# base_revA.net
KiCad netlist of a schematic drawn in EAGLE
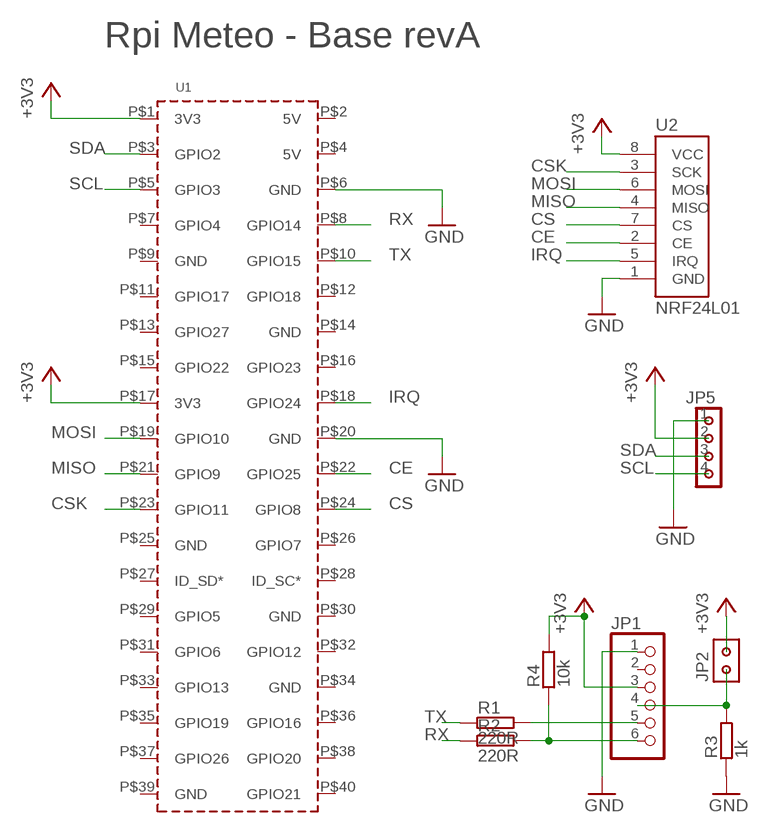
[diagram p0: schematic, sheet 1]

(export (version "E")
  (design (tool "Eeschema 10.0.6"))
  (components
    (comp (ref "JP1")
      (value "PINHD-1X6")
      (footprint "eagle-import:1X06")
      (libsource (lib "eagle-import") (part "PINHD-1X6"))
    )
    (comp (ref "JP2")
      (value "PINHD-2X1")
      (footprint "eagle-import:PINHD-2X1")
      (libsource (lib "eagle-import") (part "PINHD-2X1"))
    )
    (comp (ref "JP5")
      (value "PINHD-4X1'BASIC'")
      (footprint "eagle-import:1X04")
      (libsource (lib "eagle-import") (part "PINHD-4X1'BASIC'"))
    )
    (comp (ref "R1")
      (value "220R")
      (footprint "eagle-import:0207-10")
      (libsource (lib "eagle-import") (part "R-0207/10"))
    )
    (comp (ref "R2")
      (value "220R")
      (footprint "eagle-import:0207-10")
      (libsource (lib "eagle-import") (part "R-0207/10"))
    )
    (comp (ref "R3")
      (value "1k")
      (footprint "eagle-import:0207-10")
      (libsource (lib "eagle-import") (part "R-0207/10"))
    )
    (comp (ref "R4")
      (value "10k")
      (footprint "eagle-import:0207-10")
      (libsource (lib "eagle-import") (part "R-0207/10"))
    )
    (comp (ref "U1")
      (value "RPI3_SIMPLE'FULL'")
      (footprint "eagle-import:RPI3")
      (libsource (lib "eagle-import") (part "RPI3_SIMPLE'FULL'"))
    )
    (comp (ref "U2")
      (value "NRF24L01")
      (footprint "eagle-import:NRF24L01")
      (libsource (lib "eagle-import") (part "NRF24L01"))
    )
  )
  (nets
    (net (code "1") (name "+3V3") (class "Default")
      (node (ref "JP1") (pin "3") (pinfunction "3_3") (pintype "passive"))
      (node (ref "JP2") (pin "1") (pinfunction "1_1") (pintype "input"))
      (node (ref "JP5") (pin "2") (pinfunction "2_2") (pintype "passive"))
      (node (ref "R4") (pin "2") (pinfunction "P$2_2") (pintype "bidirectional"))
      (node (ref "U1") (pin "P$1") (pinfunction "3V3_P$1") (pintype "bidirectional"))
      (node (ref "U1") (pin "P$17") (pinfunction "3V3_P$17") (pintype "bidirectional"))
      (node (ref "U2") (pin "8") (pinfunction "VCC_8") (pintype "power_in"))
    )
    (net (code "2") (name "/CE") (class "Default")
      (node (ref "U1") (pin "P$22") (pinfunction "GPIO25_P$22") (pintype "bidirectional"))
      (node (ref "U2") (pin "2") (pinfunction "CE_2") (pintype "bidirectional"))
    )
    (net (code "3") (name "/CS") (class "Default")
      (node (ref "U1") (pin "P$24") (pinfunction "GPIO8_P$24") (pintype "bidirectional"))
      (node (ref "U2") (pin "7") (pinfunction "CS_7") (pintype "bidirectional"))
    )
    (net (code "4") (name "/CSK") (class "Default")
      (node (ref "U1") (pin "P$23") (pinfunction "GPIO11_P$23") (pintype "bidirectional"))
      (node (ref "U2") (pin "3") (pinfunction "SCK_3") (pintype "bidirectional"))
    )
    (net (code "5") (name "/IRQ") (class "Default")
      (node (ref "U1") (pin "P$18") (pinfunction "GPIO24_P$18") (pintype "bidirectional"))
      (node (ref "U2") (pin "5") (pinfunction "IRQ_5") (pintype "bidirectional"))
    )
    (net (code "6") (name "/MISO") (class "Default")
      (node (ref "U1") (pin "P$21") (pinfunction "GPIO9_P$21") (pintype "bidirectional"))
      (node (ref "U2") (pin "4") (pinfunction "MISO_4") (pintype "bidirectional"))
    )
    (net (code "7") (name "/MOSI") (class "Default")
      (node (ref "U1") (pin "P$19") (pinfunction "GPIO10_P$19") (pintype "bidirectional"))
      (node (ref "U2") (pin "6") (pinfunction "MOSI_6") (pintype "bidirectional"))
    )
    (net (code "8") (name "/RX") (class "Default")
      (node (ref "R2") (pin "1") (pinfunction "P$1_1") (pintype "bidirectional"))
      (node (ref "U1") (pin "P$8") (pinfunction "GPIO14_P$8") (pintype "bidirectional"))
    )
    (net (code "9") (name "/SCL") (class "Default")
      (node (ref "JP5") (pin "4") (pinfunction "4_4") (pintype "passive"))
      (node (ref "U1") (pin "P$5") (pinfunction "GPIO3_P$5") (pintype "bidirectional"))
    )
    (net (code "10") (name "/SDA") (class "Default")
      (node (ref "JP5") (pin "3") (pinfunction "3_3") (pintype "passive"))
      (node (ref "U1") (pin "P$3") (pinfunction "GPIO2_P$3") (pintype "bidirectional"))
    )
    (net (code "11") (name "/TX") (class "Default")
      (node (ref "R1") (pin "1") (pinfunction "P$1_1") (pintype "bidirectional"))
      (node (ref "U1") (pin "P$10") (pinfunction "GPIO15_P$10") (pintype "bidirectional"))
    )
    (net (code "12") (name "GND") (class "Default")
      (node (ref "JP1") (pin "1") (pinfunction "1_1") (pintype "passive"))
      (node (ref "JP5") (pin "1") (pinfunction "1_1") (pintype "passive"))
      (node (ref "R3") (pin "1") (pinfunction "P$1_1") (pintype "bidirectional"))
      (node (ref "U1") (pin "P$20") (pinfunction "GND_P$20") (pintype "bidirectional"))
      (node (ref "U1") (pin "P$6") (pinfunction "GND_P$6") (pintype "bidirectional"))
      (node (ref "U2") (pin "1") (pinfunction "GND_1") (pintype "power_in"))
    )
    (net (code "13") (name "Net-(R1-P$2)") (class "Default")
      (node (ref "JP1") (pin "5") (pinfunction "5_5") (pintype "passive"))
      (node (ref "R1") (pin "2") (pinfunction "P$2_2") (pintype "bidirectional"))
    )
    (net (code "14") (name "Net-(R2-P$2)") (class "Default")
      (node (ref "JP1") (pin "6") (pinfunction "6_6") (pintype "passive"))
      (node (ref "R2") (pin "2") (pinfunction "P$2_2") (pintype "bidirectional"))
      (node (ref "R4") (pin "1") (pinfunction "P$1_1") (pintype "bidirectional"))
    )
    (net (code "15") (name "Net-(R3-P$2)") (class "Default")
      (node (ref "JP1") (pin "4") (pinfunction "4_4") (pintype "passive"))
      (node (ref "JP2") (pin "2") (pinfunction "2_2") (pintype "bidirectional"))
      (node (ref "R3") (pin "2") (pinfunction "P$2_2") (pintype "bidirectional"))
    )
    (net (code "16") (name "unconnected-(JP1-Pad2)") (class "Default")
      (node (ref "JP1") (pin "2") (pinfunction "2_2") (pintype "passive"))
    )
    (net (code "17") (name "unconnected-(U1-5V-PadP$2)") (class "Default")
      (node (ref "U1") (pin "P$2") (pinfunction "5V_P$2") (pintype "bidirectional"))
    )
    (net (code "18") (name "unconnected-(U1-5V-PadP$4)") (class "Default")
      (node (ref "U1") (pin "P$4") (pinfunction "5V_P$4") (pintype "bidirectional"))
    )
    (net (code "19") (name "unconnected-(U1-GND-PadP$9)") (class "Default")
      (node (ref "U1") (pin "P$9") (pinfunction "GND_P$9") (pintype "bidirectional"))
    )
    (net (code "20") (name "unconnected-(U1-GND-PadP$14)") (class "Default")
      (node (ref "U1") (pin "P$14") (pinfunction "GND_P$14") (pintype "bidirectional"))
    )
    (net (code "21") (name "unconnected-(U1-GND-PadP$25)") (class "Default")
      (node (ref "U1") (pin "P$25") (pinfunction "GND_P$25") (pintype "bidirectional"))
    )
    (net (code "22") (name "unconnected-(U1-GND-PadP$30)") (class "Default")
      (node (ref "U1") (pin "P$30") (pinfunction "GND_P$30") (pintype "bidirectional"))
    )
    (net (code "23") (name "unconnected-(U1-GND-PadP$34)") (class "Default")
      (node (ref "U1") (pin "P$34") (pinfunction "GND_P$34") (pintype "bidirectional"))
    )
    (net (code "24") (name "unconnected-(U1-GND-PadP$39)") (class "Default")
      (node (ref "U1") (pin "P$39") (pinfunction "GND_P$39") (pintype "bidirectional"))
    )
    (net (code "25") (name "unconnected-(U1-GPIO4-PadP$7)") (class "Default")
      (node (ref "U1") (pin "P$7") (pinfunction "GPIO4_P$7") (pintype "bidirectional"))
    )
    (net (code "26") (name "unconnected-(U1-GPIO5-PadP$29)") (class "Default")
      (node (ref "U1") (pin "P$29") (pinfunction "GPIO5_P$29") (pintype "bidirectional"))
    )
    (net (code "27") (name "unconnected-(U1-GPIO6-PadP$31)") (class "Default")
      (node (ref "U1") (pin "P$31") (pinfunction "GPIO6_P$31") (pintype "bidirectional"))
    )
    (net (code "28") (name "unconnected-(U1-GPIO7-PadP$26)") (class "Default")
      (node (ref "U1") (pin "P$26") (pinfunction "GPIO7_P$26") (pintype "bidirectional"))
    )
    (net (code "29") (name "unconnected-(U1-GPIO12-PadP$32)") (class "Default")
      (node (ref "U1") (pin "P$32") (pinfunction "GPIO12_P$32") (pintype "bidirectional"))
    )
    (net (code "30") (name "unconnected-(U1-GPIO13-PadP$33)") (class "Default")
      (node (ref "U1") (pin "P$33") (pinfunction "GPIO13_P$33") (pintype "bidirectional"))
    )
    (net (code "31") (name "unconnected-(U1-GPIO16-PadP$36)") (class "Default")
      (node (ref "U1") (pin "P$36") (pinfunction "GPIO16_P$36") (pintype "bidirectional"))
    )
    (net (code "32") (name "unconnected-(U1-GPIO17-PadP$11)") (class "Default")
      (node (ref "U1") (pin "P$11") (pinfunction "GPIO17_P$11") (pintype "bidirectional"))
    )
    (net (code "33") (name "unconnected-(U1-GPIO18-PadP$12)") (class "Default")
      (node (ref "U1") (pin "P$12") (pinfunction "GPIO18_P$12") (pintype "bidirectional"))
    )
    (net (code "34") (name "unconnected-(U1-GPIO19-PadP$35)") (class "Default")
      (node (ref "U1") (pin "P$35") (pinfunction "GPIO19_P$35") (pintype "bidirectional"))
    )
    (net (code "35") (name "unconnected-(U1-GPIO20-PadP$38)") (class "Default")
      (node (ref "U1") (pin "P$38") (pinfunction "GPIO20_P$38") (pintype "bidirectional"))
    )
    (net (code "36") (name "unconnected-(U1-GPIO21-PadP$40)") (class "Default")
      (node (ref "U1") (pin "P$40") (pinfunction "GPIO21_P$40") (pintype "bidirectional"))
    )
    (net (code "37") (name "unconnected-(U1-GPIO22-PadP$15)") (class "Default")
      (node (ref "U1") (pin "P$15") (pinfunction "GPIO22_P$15") (pintype "bidirectional"))
    )
    (net (code "38") (name "unconnected-(U1-GPIO23-PadP$16)") (class "Default")
      (node (ref "U1") (pin "P$16") (pinfunction "GPIO23_P$16") (pintype "bidirectional"))
    )
    (net (code "39") (name "unconnected-(U1-GPIO26-PadP$37)") (class "Default")
      (node (ref "U1") (pin "P$37") (pinfunction "GPIO26_P$37") (pintype "bidirectional"))
    )
    (net (code "40") (name "unconnected-(U1-GPIO27-PadP$13)") (class "Default")
      (node (ref "U1") (pin "P$13") (pinfunction "GPIO27_P$13") (pintype "bidirectional"))
    )
    (net (code "41") (name "unconnected-(U1-ID_SC*-PadP$28)") (class "Default")
      (node (ref "U1") (pin "P$28") (pinfunction "ID_SC*_P$28") (pintype "bidirectional"))
    )
    (net (code "42") (name "unconnected-(U1-ID_SD*-PadP$27)") (class "Default")
      (node (ref "U1") (pin "P$27") (pinfunction "ID_SD*_P$27") (pintype "bidirectional"))
    )
  )
)
